# ESP-03_Breakout_SMT.net
KiCad netlist of a schematic drawn in EAGLE
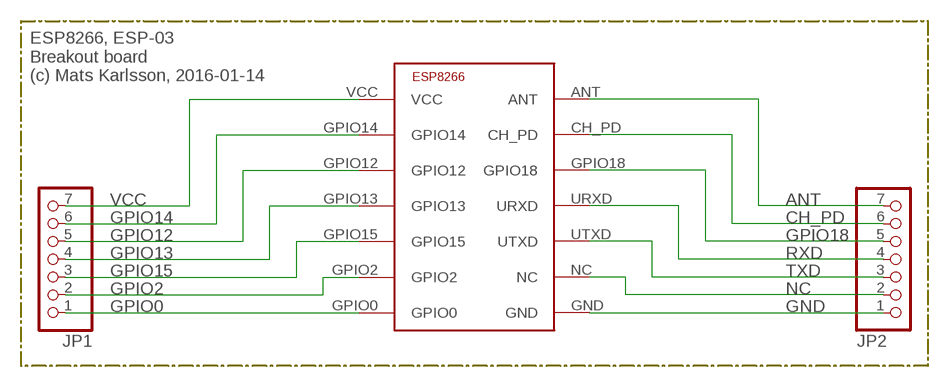
[diagram p0: schematic, sheet 1]

(export (version "E")
  (design (tool "Eeschema 10.0.6"))
  (components
    (comp (ref "JP1")
      (value "PINHD-1X71X07_SMT")
      (footprint "eagle-import:1X07_SMT")
      (libsource (lib "eagle-import") (part "PINHD-1X71X07_SMT"))
    )
    (comp (ref "JP2")
      (value "PINHD-1X71X07_SMT")
      (footprint "eagle-import:1X07_SMT")
      (libsource (lib "eagle-import") (part "PINHD-1X71X07_SMT"))
    )
    (comp (ref "U$1")
      (value "ESP8266-03")
      (footprint "eagle-import:ESP-03")
      (libsource (lib "eagle-import") (part "ESP8266-03"))
    )
  )
  (nets
    (net (code "1") (name "/ANT") (class "Default")
      (node (ref "JP2") (pin "7") (pinfunction "7_7") (pintype "passive"))
      (node (ref "U$1") (pin "ANT") (pinfunction "ANT_ANT") (pintype "bidirectional"))
    )
    (net (code "2") (name "/CH_PD") (class "Default")
      (node (ref "JP2") (pin "6") (pinfunction "6_6") (pintype "passive"))
      (node (ref "U$1") (pin "CH_PD") (pinfunction "CH_PD_CH_PD") (pintype "bidirectional"))
    )
    (net (code "3") (name "/GND") (class "Default")
      (node (ref "JP2") (pin "1") (pinfunction "1_1") (pintype "passive"))
      (node (ref "U$1") (pin "GND") (pinfunction "GND_GND") (pintype "bidirectional"))
    )
    (net (code "4") (name "/GPIO0") (class "Default")
      (node (ref "JP1") (pin "1") (pinfunction "1_1") (pintype "passive"))
      (node (ref "U$1") (pin "GPIO0") (pinfunction "GPIO0_GPIO0") (pintype "bidirectional"))
    )
    (net (code "5") (name "/GPIO2") (class "Default")
      (node (ref "JP1") (pin "2") (pinfunction "2_2") (pintype "passive"))
      (node (ref "U$1") (pin "GPIO2") (pinfunction "GPIO2_GPIO2") (pintype "bidirectional"))
    )
    (net (code "6") (name "/GPIO12") (class "Default")
      (node (ref "JP1") (pin "5") (pinfunction "5_5") (pintype "passive"))
      (node (ref "U$1") (pin "GPIO12") (pinfunction "GPIO12_GPIO12") (pintype "bidirectional"))
    )
    (net (code "7") (name "/GPIO13") (class "Default")
      (node (ref "JP1") (pin "4") (pinfunction "4_4") (pintype "passive"))
      (node (ref "U$1") (pin "GPIO13") (pinfunction "GPIO13_GPIO13") (pintype "bidirectional"))
    )
    (net (code "8") (name "/GPIO14") (class "Default")
      (node (ref "JP1") (pin "6") (pinfunction "6_6") (pintype "passive"))
      (node (ref "U$1") (pin "GPIO14") (pinfunction "GPIO14_GPIO14") (pintype "bidirectional"))
    )
    (net (code "9") (name "/GPIO15") (class "Default")
      (node (ref "JP1") (pin "3") (pinfunction "3_3") (pintype "passive"))
      (node (ref "U$1") (pin "GPIO15") (pinfunction "GPIO15_GPIO15") (pintype "bidirectional"))
    )
    (net (code "10") (name "/GPIO18") (class "Default")
      (node (ref "JP2") (pin "5") (pinfunction "5_5") (pintype "passive"))
      (node (ref "U$1") (pin "GPIO18") (pinfunction "GPIO18_GPIO18") (pintype "bidirectional"))
    )
    (net (code "11") (name "/NC") (class "Default")
      (node (ref "JP2") (pin "2") (pinfunction "2_2") (pintype "passive"))
      (node (ref "U$1") (pin "NC") (pinfunction "NC_NC") (pintype "bidirectional"))
    )
    (net (code "12") (name "/RXD") (class "Default")
      (node (ref "JP2") (pin "4") (pinfunction "4_4") (pintype "passive"))
      (node (ref "U$1") (pin "URXD") (pinfunction "URXD_URXD") (pintype "bidirectional"))
    )
    (net (code "13") (name "/TXD") (class "Default")
      (node (ref "JP2") (pin "3") (pinfunction "3_3") (pintype "passive"))
      (node (ref "U$1") (pin "UTXD") (pinfunction "UTXD_UTXD") (pintype "bidirectional"))
    )
    (net (code "14") (name "/VCC") (class "Default")
      (node (ref "JP1") (pin "7") (pinfunction "7_7") (pintype "passive"))
      (node (ref "U$1") (pin "VCC") (pinfunction "VCC_VCC") (pintype "bidirectional"))
    )
  )
)
